# mmc5983ma.net
KiCad netlist of a schematic drawn in Altium Designer
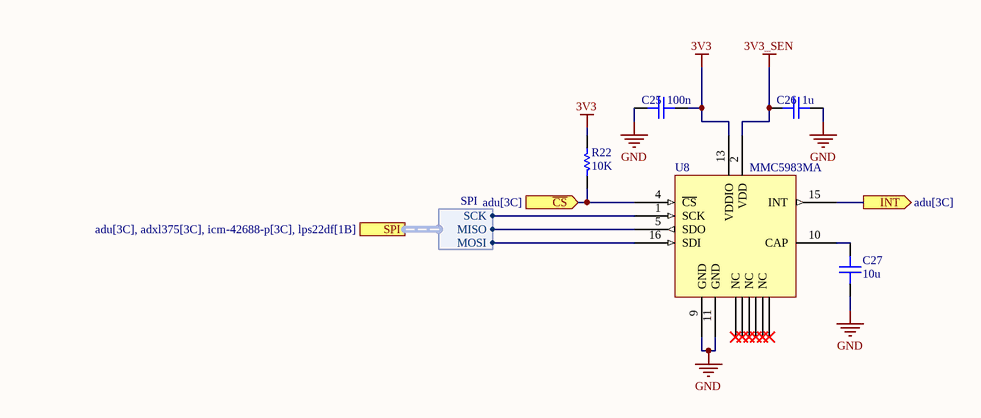
[diagram p0: mmc5983ma.SchDoc]

(export (version "E")
  (design (tool "Eeschema 10.0.6"))
  (components
    (comp (ref "C25")
      (value "100n")
      (footprint "CAP-0603-NP")
      (description "Capacitor")
      (libsource (lib "drfc_schlib") (part "Capacitor"))
    )
    (comp (ref "C26")
      (value "1u")
      (footprint "CAP-0603-NP")
      (description "Capacitor")
      (libsource (lib "drfc_schlib") (part "Capacitor"))
    )
    (comp (ref "C27")
      (value "10u")
      (footprint "CAP-0603-NP")
      (description "Capacitor")
      (libsource (lib "drfc_schlib") (part "Capacitor"))
    )
    (comp (ref "R22")
      (value "10K")
      (footprint "RES-0603")
      (description "Resistor")
      (libsource (lib "drfc_schlib") (part "Resistor"))
    )
    (comp (ref "U8")
      (value "MMC5983MA")
      (footprint "MMC5983MA")
      (description "±8 Gauss, High Performance\r\n3-axis Magnetic Sensor")
      (libsource (lib "drfc_schlib") (part "MMC5983MA"))
    )
  )
  (nets
    (net (code "2") (name "/INT") (class "Default")
      (node (ref "U8") (pin "15") (pinfunction "INT_15") (pintype "output"))
    )
    (net (code "3") (name "/MISO") (class "Default")
      (node (ref "U8") (pin "5") (pinfunction "SDO_5") (pintype "output"))
    )
    (net (code "4") (name "/MOSI") (class "Default")
      (node (ref "U8") (pin "16") (pinfunction "SDI_16") (pintype "input"))
    )
    (net (code "5") (name "/SCK") (class "Default")
      (node (ref "U8") (pin "1") (pinfunction "SCK_1") (pintype "input"))
    )
    (net (code "7") (name "/~{CS}") (class "Default")
      (node (ref "R22") (pin "1") (pinfunction "1_1") (pintype "passive"))
      (node (ref "U8") (pin "4") (pinfunction "~{CS}_4") (pintype "input"))
    )
    (net (code "8") (name "3V3") (class "Default")
      (node (ref "C25") (pin "2") (pinfunction "2_2") (pintype "passive"))
      (node (ref "R22") (pin "2") (pinfunction "2_2") (pintype "passive"))
      (node (ref "U8") (pin "13") (pinfunction "VDDIO_13") (pintype "power_in"))
    )
    (net (code "9") (name "3V3_SEN") (class "Default")
      (node (ref "C26") (pin "1") (pinfunction "1_1") (pintype "passive"))
      (node (ref "U8") (pin "2") (pinfunction "VDD_2") (pintype "power_in"))
    )
    (net (code "10") (name "GND") (class "Default")
      (node (ref "C25") (pin "1") (pinfunction "1_1") (pintype "passive"))
      (node (ref "C26") (pin "2") (pinfunction "2_2") (pintype "passive"))
      (node (ref "C27") (pin "1") (pinfunction "1_1") (pintype "passive"))
      (node (ref "U8") (pin "11") (pinfunction "GND_11") (pintype "power_in"))
      (node (ref "U8") (pin "9") (pinfunction "GND_9") (pintype "power_in"))
    )
    (net (code "11") (name "Net-(U8-CAP)") (class "Default")
      (node (ref "C27") (pin "2") (pinfunction "2_2") (pintype "passive"))
      (node (ref "U8") (pin "10") (pinfunction "CAP_10") (pintype "power_in"))
    )
    (net (code "12") (name "unconnected-(U8-NC-Pad3)") (class "Default")
      (node (ref "U8") (pin "3") (pinfunction "NC_3") (pintype "passive+no_connect"))
    )
    (net (code "13") (name "unconnected-(U8-NC-Pad6)") (class "Default")
      (node (ref "U8") (pin "6") (pinfunction "NC_6") (pintype "passive+no_connect"))
    )
    (net (code "14") (name "unconnected-(U8-NC-Pad7)") (class "Default")
      (node (ref "U8") (pin "7") (pinfunction "NC_7") (pintype "passive+no_connect"))
    )
    (net (code "15") (name "unconnected-(U8-NC-Pad8)") (class "Default")
      (node (ref "U8") (pin "8") (pinfunction "NC_8") (pintype "passive+no_connect"))
    )
    (net (code "16") (name "unconnected-(U8-NC-Pad12)") (class "Default")
      (node (ref "U8") (pin "12") (pinfunction "NC_12") (pintype "passive+no_connect"))
    )
    (net (code "17") (name "unconnected-(U8-NC-Pad14)") (class "Default")
      (node (ref "U8") (pin "14") (pinfunction "NC_14") (pintype "passive+no_connect"))
    )
  )
)
